# MainConnector.net
KiCad netlist of a schematic drawn in Altium Designer
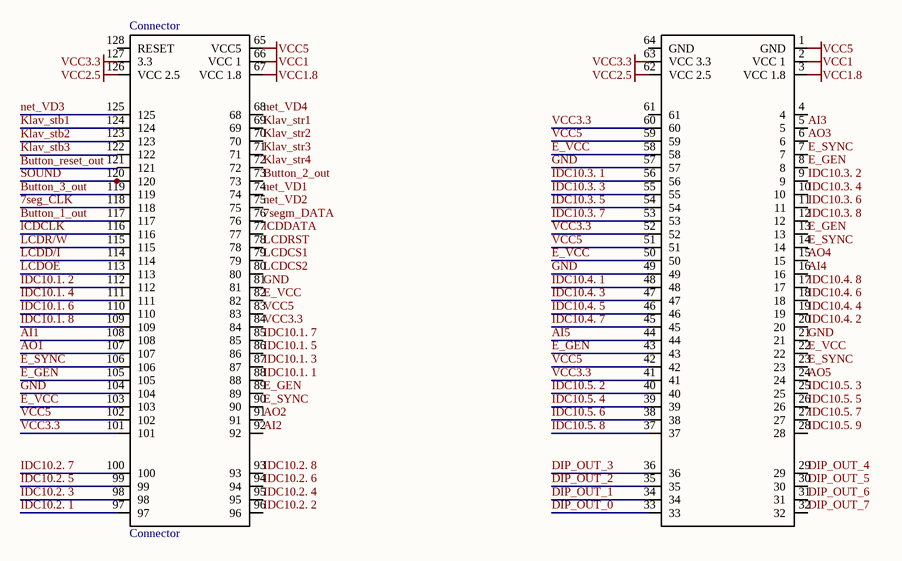
[diagram p0: MainConnector.SchDoc]

(export (version "E")
  (design (tool "Eeschema 10.0.6"))
  (components
    (comp (ref "Connector")
      (value "Connector")
      (footprint "PcbLib1:Connect")
      (libsource (lib "Library") (part "Connector"))
    )
  )
  (nets
    (net (code "1") (name "/7seg_CLK") (class "Default")
      (node (ref "Connector") (pin "118") (pinfunction "118_118") (pintype "passive"))
    )
    (net (code "2") (name "/7segm_DATA") (class "Default")
      (node (ref "Connector") (pin "76") (pinfunction "76_76") (pintype "passive"))
    )
    (net (code "3") (name "/AI1") (class "Default")
      (node (ref "Connector") (pin "108") (pinfunction "108_108") (pintype "passive"))
    )
    (net (code "4") (name "/AI2") (class "Default")
      (node (ref "Connector") (pin "92") (pinfunction "92_92") (pintype "passive"))
    )
    (net (code "5") (name "/AI3") (class "Default")
      (node (ref "Connector") (pin "5") (pinfunction "5_5") (pintype "passive"))
    )
    (net (code "6") (name "/AI4") (class "Default")
      (node (ref "Connector") (pin "16") (pinfunction "16_16") (pintype "passive"))
    )
    (net (code "7") (name "/AI5") (class "Default")
      (node (ref "Connector") (pin "44") (pinfunction "44_44") (pintype "passive"))
    )
    (net (code "8") (name "/AO1") (class "Default")
      (node (ref "Connector") (pin "107") (pinfunction "107_107") (pintype "passive"))
    )
    (net (code "9") (name "/AO2") (class "Default")
      (node (ref "Connector") (pin "91") (pinfunction "91_91") (pintype "passive"))
    )
    (net (code "10") (name "/AO3") (class "Default")
      (node (ref "Connector") (pin "6") (pinfunction "6_6") (pintype "passive"))
    )
    (net (code "11") (name "/AO4") (class "Default")
      (node (ref "Connector") (pin "15") (pinfunction "15_15") (pintype "passive"))
    )
    (net (code "12") (name "/AO5") (class "Default")
      (node (ref "Connector") (pin "24") (pinfunction "24_24") (pintype "passive"))
    )
    (net (code "13") (name "/Button_1_out") (class "Default")
      (node (ref "Connector") (pin "117") (pinfunction "117_117") (pintype "passive"))
    )
    (net (code "14") (name "/Button_2_out") (class "Default")
      (node (ref "Connector") (pin "73") (pinfunction "73_73") (pintype "passive"))
    )
    (net (code "15") (name "/Button_3_out") (class "Default")
      (node (ref "Connector") (pin "119") (pinfunction "119_119") (pintype "passive"))
    )
    (net (code "16") (name "/Button_reset_out") (class "Default")
      (node (ref "Connector") (pin "121") (pinfunction "121_121") (pintype "passive"))
    )
    (net (code "17") (name "/DIP_OUT_0") (class "Default")
      (node (ref "Connector") (pin "33") (pinfunction "33_33") (pintype "passive"))
    )
    (net (code "18") (name "/DIP_OUT_1") (class "Default")
      (node (ref "Connector") (pin "34") (pinfunction "34_34") (pintype "passive"))
    )
    (net (code "19") (name "/DIP_OUT_2") (class "Default")
      (node (ref "Connector") (pin "35") (pinfunction "35_35") (pintype "passive"))
    )
    (net (code "20") (name "/DIP_OUT_3") (class "Default")
      (node (ref "Connector") (pin "36") (pinfunction "36_36") (pintype "passive"))
    )
    (net (code "21") (name "/DIP_OUT_4") (class "Default")
      (node (ref "Connector") (pin "29") (pinfunction "29_29") (pintype "passive"))
    )
    (net (code "22") (name "/DIP_OUT_5") (class "Default")
      (node (ref "Connector") (pin "30") (pinfunction "30_30") (pintype "passive"))
    )
    (net (code "23") (name "/DIP_OUT_6") (class "Default")
      (node (ref "Connector") (pin "31") (pinfunction "31_31") (pintype "passive"))
    )
    (net (code "24") (name "/DIP_OUT_7") (class "Default")
      (node (ref "Connector") (pin "32") (pinfunction "32_32") (pintype "passive"))
    )
    (net (code "25") (name "/E_GEN") (class "Default")
      (node (ref "Connector") (pin "105") (pinfunction "105_105") (pintype "passive"))
      (node (ref "Connector") (pin "13") (pinfunction "13_13") (pintype "passive"))
      (node (ref "Connector") (pin "43") (pinfunction "43_43") (pintype "passive"))
      (node (ref "Connector") (pin "8") (pinfunction "8_8") (pintype "passive"))
      (node (ref "Connector") (pin "89") (pinfunction "89_89") (pintype "passive"))
    )
    (net (code "26") (name "/E_SYNC") (class "Default")
      (node (ref "Connector") (pin "106") (pinfunction "106_106") (pintype "passive"))
      (node (ref "Connector") (pin "14") (pinfunction "14_14") (pintype "passive"))
      (node (ref "Connector") (pin "23") (pinfunction "23_23") (pintype "passive"))
      (node (ref "Connector") (pin "7") (pinfunction "7_7") (pintype "passive"))
      (node (ref "Connector") (pin "90") (pinfunction "90_90") (pintype "passive"))
    )
    (net (code "27") (name "/E_VCC") (class "Default")
      (node (ref "Connector") (pin "103") (pinfunction "103_103") (pintype "passive"))
      (node (ref "Connector") (pin "22") (pinfunction "22_22") (pintype "passive"))
      (node (ref "Connector") (pin "50") (pinfunction "50_50") (pintype "passive"))
      (node (ref "Connector") (pin "58") (pinfunction "58_58") (pintype "passive"))
      (node (ref "Connector") (pin "82") (pinfunction "82_82") (pintype "passive"))
    )
    (net (code "28") (name "/GND") (class "Default")
      (node (ref "Connector") (pin "104") (pinfunction "104_104") (pintype "passive"))
      (node (ref "Connector") (pin "21") (pinfunction "21_21") (pintype "passive"))
      (node (ref "Connector") (pin "49") (pinfunction "49_49") (pintype "passive"))
      (node (ref "Connector") (pin "57") (pinfunction "57_57") (pintype "passive"))
      (node (ref "Connector") (pin "81") (pinfunction "81_81") (pintype "passive"))
    )
    (net (code "29") (name "/IDC10.1. 1") (class "Default")
      (node (ref "Connector") (pin "88") (pinfunction "88_88") (pintype "passive"))
    )
    (net (code "30") (name "/IDC10.1. 2") (class "Default")
      (node (ref "Connector") (pin "112") (pinfunction "112_112") (pintype "passive"))
    )
    (net (code "31") (name "/IDC10.1. 3") (class "Default")
      (node (ref "Connector") (pin "87") (pinfunction "87_87") (pintype "passive"))
    )
    (net (code "32") (name "/IDC10.1. 4") (class "Default")
      (node (ref "Connector") (pin "111") (pinfunction "111_111") (pintype "passive"))
    )
    (net (code "33") (name "/IDC10.1. 5") (class "Default")
      (node (ref "Connector") (pin "86") (pinfunction "86_86") (pintype "passive"))
    )
    (net (code "34") (name "/IDC10.1. 6") (class "Default")
      (node (ref "Connector") (pin "110") (pinfunction "110_110") (pintype "passive"))
    )
    (net (code "35") (name "/IDC10.1. 7") (class "Default")
      (node (ref "Connector") (pin "85") (pinfunction "85_85") (pintype "passive"))
    )
    (net (code "36") (name "/IDC10.1. 8") (class "Default")
      (node (ref "Connector") (pin "109") (pinfunction "109_109") (pintype "passive"))
    )
    (net (code "37") (name "/IDC10.2. 1") (class "Default")
      (node (ref "Connector") (pin "97") (pinfunction "97_97") (pintype "passive"))
    )
    (net (code "38") (name "/IDC10.2. 2") (class "Default")
      (node (ref "Connector") (pin "96") (pinfunction "96_96") (pintype "passive"))
    )
    (net (code "39") (name "/IDC10.2. 3") (class "Default")
      (node (ref "Connector") (pin "98") (pinfunction "98_98") (pintype "passive"))
    )
    (net (code "40") (name "/IDC10.2. 4") (class "Default")
      (node (ref "Connector") (pin "95") (pinfunction "95_95") (pintype "passive"))
    )
    (net (code "41") (name "/IDC10.2. 5") (class "Default")
      (node (ref "Connector") (pin "99") (pinfunction "99_99") (pintype "passive"))
    )
    (net (code "42") (name "/IDC10.2. 6") (class "Default")
      (node (ref "Connector") (pin "94") (pinfunction "94_94") (pintype "passive"))
    )
    (net (code "43") (name "/IDC10.2. 7") (class "Default")
      (node (ref "Connector") (pin "100") (pinfunction "100_100") (pintype "passive"))
    )
    (net (code "44") (name "/IDC10.2. 8") (class "Default")
      (node (ref "Connector") (pin "93") (pinfunction "93_93") (pintype "passive"))
    )
    (net (code "45") (name "/IDC10.3. 1") (class "Default")
      (node (ref "Connector") (pin "56") (pinfunction "56_56") (pintype "passive"))
    )
    (net (code "46") (name "/IDC10.3. 2") (class "Default")
      (node (ref "Connector") (pin "9") (pinfunction "9_9") (pintype "passive"))
    )
    (net (code "47") (name "/IDC10.3. 3") (class "Default")
      (node (ref "Connector") (pin "55") (pinfunction "55_55") (pintype "passive"))
    )
    (net (code "48") (name "/IDC10.3. 4") (class "Default")
      (node (ref "Connector") (pin "10") (pinfunction "10_10") (pintype "passive"))
    )
    (net (code "49") (name "/IDC10.3. 5") (class "Default")
      (node (ref "Connector") (pin "54") (pinfunction "54_54") (pintype "passive"))
    )
    (net (code "50") (name "/IDC10.3. 6") (class "Default")
      (node (ref "Connector") (pin "11") (pinfunction "11_11") (pintype "passive"))
    )
    (net (code "51") (name "/IDC10.3. 7") (class "Default")
      (node (ref "Connector") (pin "53") (pinfunction "53_53") (pintype "passive"))
    )
    (net (code "52") (name "/IDC10.3. 8") (class "Default")
      (node (ref "Connector") (pin "12") (pinfunction "12_12") (pintype "passive"))
    )
    (net (code "53") (name "/IDC10.4. 1") (class "Default")
      (node (ref "Connector") (pin "48") (pinfunction "48_48") (pintype "passive"))
    )
    (net (code "54") (name "/IDC10.4. 2") (class "Default")
      (node (ref "Connector") (pin "20") (pinfunction "20_20") (pintype "passive"))
    )
    (net (code "55") (name "/IDC10.4. 3") (class "Default")
      (node (ref "Connector") (pin "47") (pinfunction "47_47") (pintype "passive"))
    )
    (net (code "56") (name "/IDC10.4. 4") (class "Default")
      (node (ref "Connector") (pin "19") (pinfunction "19_19") (pintype "passive"))
    )
    (net (code "57") (name "/IDC10.4. 5") (class "Default")
      (node (ref "Connector") (pin "46") (pinfunction "46_46") (pintype "passive"))
    )
    (net (code "58") (name "/IDC10.4. 6") (class "Default")
      (node (ref "Connector") (pin "18") (pinfunction "18_18") (pintype "passive"))
    )
    (net (code "59") (name "/IDC10.4. 7") (class "Default")
      (node (ref "Connector") (pin "45") (pinfunction "45_45") (pintype "passive"))
    )
    (net (code "60") (name "/IDC10.4. 8") (class "Default")
      (node (ref "Connector") (pin "17") (pinfunction "17_17") (pintype "passive"))
    )
    (net (code "61") (name "/IDC10.5. 2") (class "Default")
      (node (ref "Connector") (pin "40") (pinfunction "40_40") (pintype "passive"))
    )
    (net (code "62") (name "/IDC10.5. 3") (class "Default")
      (node (ref "Connector") (pin "25") (pinfunction "25_25") (pintype "passive"))
    )
    (net (code "63") (name "/IDC10.5. 4") (class "Default")
      (node (ref "Connector") (pin "39") (pinfunction "39_39") (pintype "passive"))
    )
    (net (code "64") (name "/IDC10.5. 5") (class "Default")
      (node (ref "Connector") (pin "26") (pinfunction "26_26") (pintype "passive"))
    )
    (net (code "65") (name "/IDC10.5. 6") (class "Default")
      (node (ref "Connector") (pin "38") (pinfunction "38_38") (pintype "passive"))
    )
    (net (code "66") (name "/IDC10.5. 7") (class "Default")
      (node (ref "Connector") (pin "27") (pinfunction "27_27") (pintype "passive"))
    )
    (net (code "67") (name "/IDC10.5. 8") (class "Default")
      (node (ref "Connector") (pin "37") (pinfunction "37_37") (pintype "passive"))
    )
    (net (code "68") (name "/IDC10.5. 9") (class "Default")
      (node (ref "Connector") (pin "28") (pinfunction "28_28") (pintype "passive"))
    )
    (net (code "69") (name "/Klav_stb1") (class "Default")
      (node (ref "Connector") (pin "124") (pinfunction "124_124") (pintype "passive"))
    )
    (net (code "70") (name "/Klav_stb2") (class "Default")
      (node (ref "Connector") (pin "123") (pinfunction "123_123") (pintype "passive"))
    )
    (net (code "71") (name "/Klav_stb3") (class "Default")
      (node (ref "Connector") (pin "122") (pinfunction "122_122") (pintype "passive"))
    )
    (net (code "72") (name "/Klav_str1") (class "Default")
      (node (ref "Connector") (pin "69") (pinfunction "69_69") (pintype "passive"))
    )
    (net (code "73") (name "/Klav_str2") (class "Default")
      (node (ref "Connector") (pin "70") (pinfunction "70_70") (pintype "passive"))
    )
    (net (code "74") (name "/Klav_str3") (class "Default")
      (node (ref "Connector") (pin "71") (pinfunction "71_71") (pintype "passive"))
    )
    (net (code "75") (name "/Klav_str4") (class "Default")
      (node (ref "Connector") (pin "72") (pinfunction "72_72") (pintype "passive"))
    )
    (net (code "76") (name "/LCDCS1") (class "Default")
      (node (ref "Connector") (pin "79") (pinfunction "79_79") (pintype "passive"))
    )
    (net (code "77") (name "/LCDCS2") (class "Default")
      (node (ref "Connector") (pin "80") (pinfunction "80_80") (pintype "passive"))
    )
    (net (code "78") (name "/LCDD{slash}I") (class "Default")
      (node (ref "Connector") (pin "114") (pinfunction "114_114") (pintype "passive"))
    )
    (net (code "79") (name "/LCDOE") (class "Default")
      (node (ref "Connector") (pin "113") (pinfunction "113_113") (pintype "passive"))
    )
    (net (code "80") (name "/LCDRST") (class "Default")
      (node (ref "Connector") (pin "78") (pinfunction "78_78") (pintype "passive"))
    )
    (net (code "81") (name "/LCDR{slash}W") (class "Default")
      (node (ref "Connector") (pin "115") (pinfunction "115_115") (pintype "passive"))
    )
    (net (code "82") (name "/SOUND") (class "Default")
      (node (ref "Connector") (pin "120") (pinfunction "120_120") (pintype "passive"))
    )
    (net (code "83") (name "/lCDCLK") (class "Default")
      (node (ref "Connector") (pin "116") (pinfunction "116_116") (pintype "passive"))
    )
    (net (code "84") (name "/lCDDATA") (class "Default")
      (node (ref "Connector") (pin "77") (pinfunction "77_77") (pintype "passive"))
    )
    (net (code "85") (name "/net_VD1") (class "Default")
      (node (ref "Connector") (pin "74") (pinfunction "74_74") (pintype "passive"))
    )
    (net (code "86") (name "/net_VD2") (class "Default")
      (node (ref "Connector") (pin "75") (pinfunction "75_75") (pintype "passive"))
    )
    (net (code "87") (name "/net_VD3") (class "Default")
      (node (ref "Connector") (pin "125") (pinfunction "125_125") (pintype "passive"))
    )
    (net (code "88") (name "/net_VD4") (class "Default")
      (node (ref "Connector") (pin "68") (pinfunction "68_68") (pintype "passive"))
    )
    (net (code "89") (name "VCC1") (class "Default")
      (node (ref "Connector") (pin "2") (pinfunction "VCC_1_2") (pintype "passive"))
      (node (ref "Connector") (pin "66") (pinfunction "VCC_1_66") (pintype "passive"))
    )
    (net (code "90") (name "VCC1.8") (class "Default")
      (node (ref "Connector") (pin "3") (pinfunction "VCC_1.8_3") (pintype "passive"))
      (node (ref "Connector") (pin "67") (pinfunction "VCC_1.8_67") (pintype "passive"))
    )
    (net (code "91") (name "VCC2.5") (class "Default")
      (node (ref "Connector") (pin "126") (pinfunction "VCC_2.5_126") (pintype "passive"))
      (node (ref "Connector") (pin "62") (pinfunction "VCC_2.5_62") (pintype "passive"))
    )
    (net (code "92") (name "VCC3.3") (class "Default")
      (node (ref "Connector") (pin "101") (pinfunction "101_101") (pintype "passive"))
      (node (ref "Connector") (pin "127") (pinfunction "3.3_127") (pintype "passive"))
      (node (ref "Connector") (pin "41") (pinfunction "41_41") (pintype "passive"))
      (node (ref "Connector") (pin "52") (pinfunction "52_52") (pintype "passive"))
      (node (ref "Connector") (pin "60") (pinfunction "60_60") (pintype "passive"))
      (node (ref "Connector") (pin "63") (pinfunction "VCC_3.3_63") (pintype "passive"))
      (node (ref "Connector") (pin "84") (pinfunction "84_84") (pintype "passive"))
    )
    (net (code "93") (name "VCC5") (class "Default")
      (node (ref "Connector") (pin "1") (pinfunction "GND_1") (pintype "passive"))
      (node (ref "Connector") (pin "102") (pinfunction "102_102") (pintype "passive"))
      (node (ref "Connector") (pin "42") (pinfunction "42_42") (pintype "passive"))
      (node (ref "Connector") (pin "51") (pinfunction "51_51") (pintype "passive"))
      (node (ref "Connector") (pin "59") (pinfunction "59_59") (pintype "passive"))
      (node (ref "Connector") (pin "65") (pinfunction "VCC5_65") (pintype "passive"))
      (node (ref "Connector") (pin "83") (pinfunction "83_83") (pintype "passive"))
    )
    (net (code "94") (name "unconnected-(Connector-GND-Pad64)") (class "Default")
      (node (ref "Connector") (pin "64") (pinfunction "GND_64") (pintype "passive"))
    )
    (net (code "95") (name "unconnected-(Connector-Pad4)") (class "Default")
      (node (ref "Connector") (pin "4") (pinfunction "4_4") (pintype "passive"))
    )
    (net (code "96") (name "unconnected-(Connector-Pad61)") (class "Default")
      (node (ref "Connector") (pin "61") (pinfunction "61_61") (pintype "passive"))
    )
    (net (code "97") (name "unconnected-(Connector-RESET-Pad128)") (class "Default")
      (node (ref "Connector") (pin "128") (pinfunction "RESET_128") (pintype "passive"))
    )
  )
)
